# passive-optothing.net
KiCad netlist of a schematic drawn in EAGLE
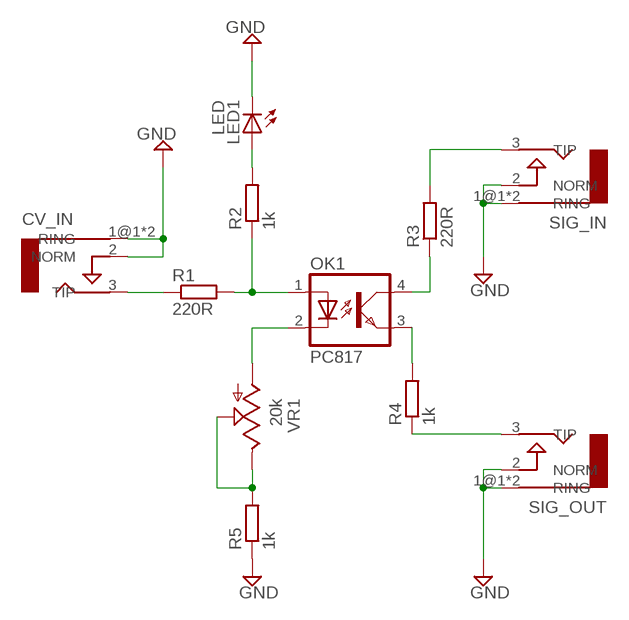
[diagram p0: schematic, sheet 1]

(export (version "E")
  (design (tool "Eeschema 10.0.6"))
  (components
    (comp (ref "CV_IN")
      (value "AUDIO-JACKERTHENVAR")
      (footprint "eagle-import:ERTHENVAR-JACK")
      (libsource (lib "eagle-import") (part "AUDIO-JACKERTHENVAR"))
    )
    (comp (ref "LED1")
      (value "LED")
      (footprint "eagle-import:CHIPLED_0805")
      (libsource (lib "eagle-import") (part "LEDCHIPLED_0805"))
    )
    (comp (ref "OK1")
      (value "PC817")
      (footprint "eagle-import:DIL04")
      (fields (field (name "MPN") "PC817X4J000F"))
      (libsource (lib "eagle-import") (part "PC817"))
    )
    (comp (ref "R1")
      (value "220R")
      (footprint "eagle-import:R0805")
      (libsource (lib "eagle-import") (part "R-EU_R0805"))
    )
    (comp (ref "R2")
      (value "1k")
      (footprint "eagle-import:R0805")
      (libsource (lib "eagle-import") (part "R-EU_R0805"))
    )
    (comp (ref "R3")
      (value "220R")
      (footprint "eagle-import:R0805")
      (libsource (lib "eagle-import") (part "R-EU_R0805"))
    )
    (comp (ref "R4")
      (value "1k")
      (footprint "eagle-import:R0805")
      (libsource (lib "eagle-import") (part "R-EU_R0805"))
    )
    (comp (ref "R5")
      (value "1k")
      (footprint "eagle-import:R0805")
      (libsource (lib "eagle-import") (part "R-EU_R0805"))
    )
    (comp (ref "SIG_IN")
      (value "AUDIO-JACKERTHENVAR")
      (footprint "eagle-import:ERTHENVAR-JACK")
      (libsource (lib "eagle-import") (part "AUDIO-JACKERTHENVAR"))
    )
    (comp (ref "SIG_OUT")
      (value "AUDIO-JACKERTHENVAR")
      (footprint "eagle-import:ERTHENVAR-JACK")
      (libsource (lib "eagle-import") (part "AUDIO-JACKERTHENVAR"))
    )
    (comp (ref "VR1")
      (value "20k")
      (footprint "eagle-import:9MM_SNAP-IN_POT")
      (libsource (lib "eagle-import") (part "9MM_SNAP-IN_POT_"))
    )
  )
  (nets
    (net (code "1") (name "GND") (class "Default")
      (node (ref "CV_IN") (pin "1@1") (pinfunction "RING_1@1") (pintype "bidirectional"))
      (node (ref "CV_IN") (pin "1@2") (pinfunction "RING_1@2") (pintype "bidirectional"))
      (node (ref "CV_IN") (pin "2") (pinfunction "NORM_2") (pintype "bidirectional"))
      (node (ref "LED1") (pin "C") (pinfunction "C_C") (pintype "passive"))
      (node (ref "R5") (pin "1") (pinfunction "1_1") (pintype "passive"))
      (node (ref "SIG_IN") (pin "1@1") (pinfunction "RING_1@1") (pintype "bidirectional"))
      (node (ref "SIG_IN") (pin "1@2") (pinfunction "RING_1@2") (pintype "bidirectional"))
      (node (ref "SIG_IN") (pin "2") (pinfunction "NORM_2") (pintype "bidirectional"))
      (node (ref "SIG_OUT") (pin "1@1") (pinfunction "RING_1@1") (pintype "bidirectional"))
      (node (ref "SIG_OUT") (pin "1@2") (pinfunction "RING_1@2") (pintype "bidirectional"))
      (node (ref "SIG_OUT") (pin "2") (pinfunction "NORM_2") (pintype "bidirectional"))
    )
    (net (code "2") (name "Net-(CV_IN-TIP)") (class "Default")
      (node (ref "CV_IN") (pin "3") (pinfunction "TIP_3") (pintype "bidirectional"))
      (node (ref "R1") (pin "1") (pinfunction "1_1") (pintype "passive"))
    )
    (net (code "3") (name "Net-(LED1-PadA)") (class "Default")
      (node (ref "LED1") (pin "A") (pinfunction "A_A") (pintype "passive"))
      (node (ref "R2") (pin "2") (pinfunction "2_2") (pintype "passive"))
    )
    (net (code "4") (name "Net-(OK1-A)") (class "Default")
      (node (ref "OK1") (pin "1") (pinfunction "A_1") (pintype "passive"))
      (node (ref "R1") (pin "2") (pinfunction "2_2") (pintype "passive"))
      (node (ref "R2") (pin "1") (pinfunction "1_1") (pintype "passive"))
    )
    (net (code "5") (name "Net-(OK1-C)") (class "Default")
      (node (ref "OK1") (pin "2") (pinfunction "C_2") (pintype "passive"))
      (node (ref "VR1") (pin "1") (pinfunction "A_1") (pintype "passive"))
    )
    (net (code "6") (name "Net-(OK1-COL)") (class "Default")
      (node (ref "OK1") (pin "4") (pinfunction "COL_4") (pintype "passive"))
      (node (ref "R3") (pin "1") (pinfunction "1_1") (pintype "passive"))
    )
    (net (code "7") (name "Net-(OK1-EMIT)") (class "Default")
      (node (ref "OK1") (pin "3") (pinfunction "EMIT_3") (pintype "passive"))
      (node (ref "R4") (pin "2") (pinfunction "2_2") (pintype "passive"))
    )
    (net (code "8") (name "Net-(SIG_IN-TIP)") (class "Default")
      (node (ref "R3") (pin "2") (pinfunction "2_2") (pintype "passive"))
      (node (ref "SIG_IN") (pin "3") (pinfunction "TIP_3") (pintype "bidirectional"))
    )
    (net (code "9") (name "Net-(SIG_OUT-TIP)") (class "Default")
      (node (ref "R4") (pin "1") (pinfunction "1_1") (pintype "passive"))
      (node (ref "SIG_OUT") (pin "3") (pinfunction "TIP_3") (pintype "bidirectional"))
    )
    (net (code "10") (name "Net-(VR1-E)") (class "Default")
      (node (ref "R5") (pin "2") (pinfunction "2_2") (pintype "passive"))
      (node (ref "VR1") (pin "2") (pinfunction "S_2") (pintype "passive"))
      (node (ref "VR1") (pin "3") (pinfunction "E_3") (pintype "passive"))
    )
  )
)
